# Current_sensor.net
KiCad netlist of a schematic drawn in EAGLE
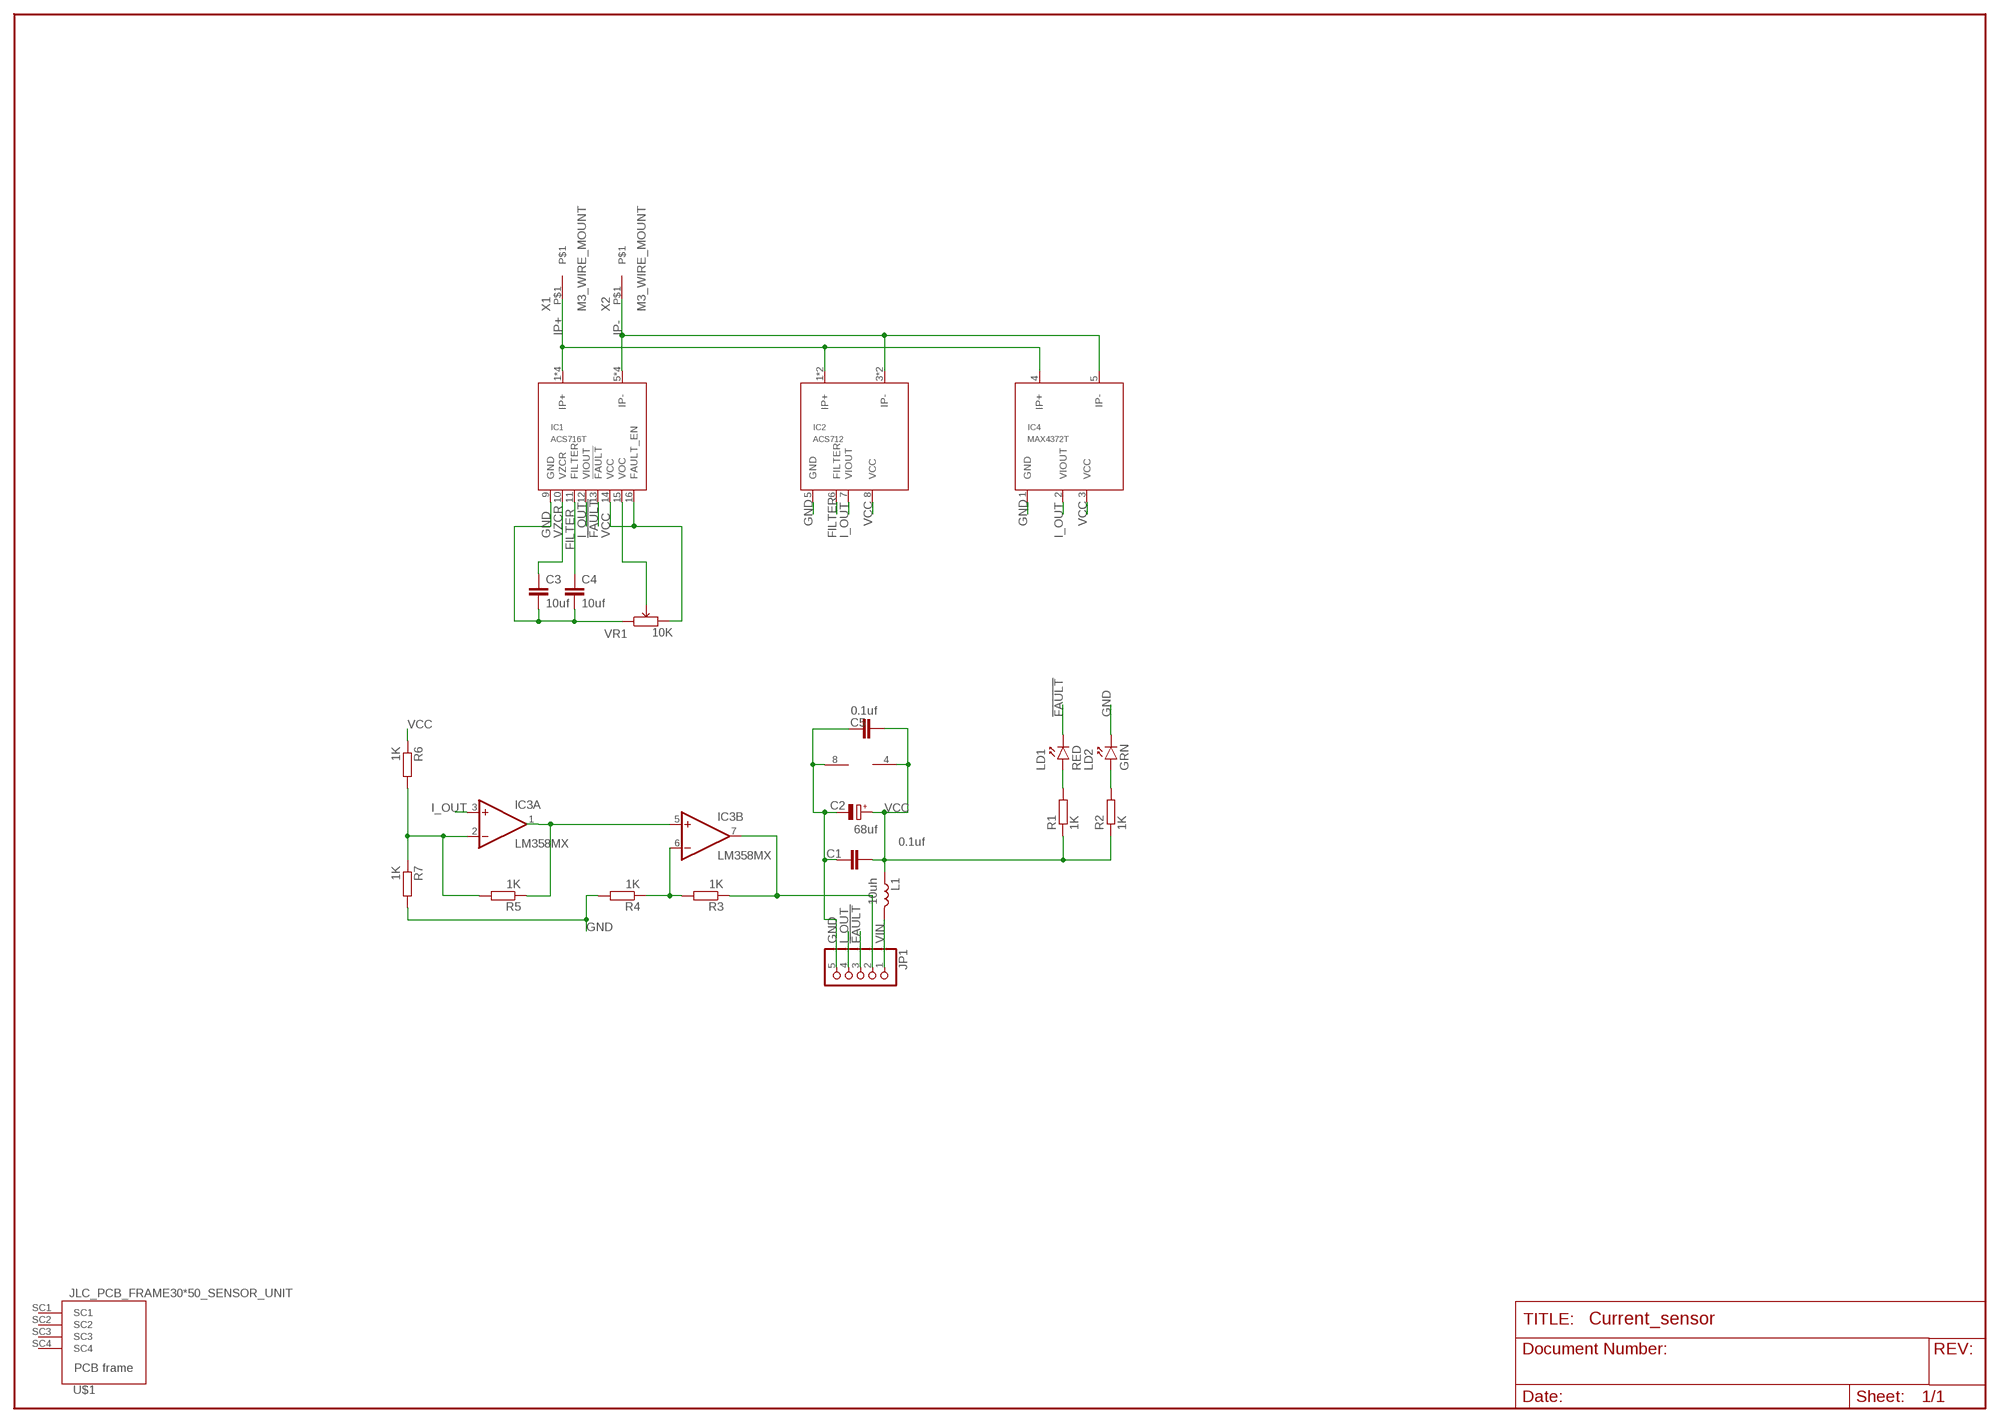
[diagram p0: schematic, sheet 1]

(export (version "E")
  (design (tool "Eeschema 10.0.6"))
  (components
    (comp (ref "C1")
      (value "0.1uf")
      (footprint "eagle-import:0603")
      (libsource (lib "eagle-import") (part "SMD_C0603"))
    )
    (comp (ref "C2")
      (value "68uf")
      (footprint "eagle-import:D_7343-31R")
      (libsource (lib "eagle-import") (part "TANTAL_686_7343"))
    )
    (comp (ref "C3")
      (value "10uf")
      (footprint "eagle-import:0805")
      (libsource (lib "eagle-import") (part "SMD_C0805"))
    )
    (comp (ref "C4")
      (value "10uf")
      (footprint "eagle-import:0805")
      (libsource (lib "eagle-import") (part "SMD_C0805"))
    )
    (comp (ref "C5")
      (value "0.1uf")
      (footprint "eagle-import:0603")
      (libsource (lib "eagle-import") (part "SMD_C0603"))
    )
    (comp (ref "IC1")
      (value "ACS716T")
      (footprint "eagle-import:SO16L")
      (libsource (lib "eagle-import") (part "ACS716T"))
    )
    (comp (ref "IC2")
      (value "ACS712")
      (footprint "eagle-import:SO8")
      (libsource (lib "eagle-import") (part "ACS712"))
    )
    (comp (ref "IC3")
      (value "LM358MX")
      (footprint "eagle-import:SO08")
      (libsource (lib "eagle-import") (part "LM358MX"))
    )
    (comp (ref "IC4")
      (value "MAX4372T")
      (footprint "eagle-import:SOT-23(5)")
      (libsource (lib "eagle-import") (part "MAX4372T"))
    )
    (comp (ref "JP1")
      (value "PINHD-1X55X2MM")
      (footprint "eagle-import:1_05X2MM")
      (libsource (lib "eagle-import") (part "PINHD-1X55X2MM"))
    )
    (comp (ref "L1")
      (value "10uh")
      (footprint "eagle-import:0603")
      (libsource (lib "eagle-import") (part "SMD_L0603"))
    )
    (comp (ref "LD1")
      (value "RED")
      (footprint "eagle-import:0603_P")
      (libsource (lib "eagle-import") (part "LED0603"))
    )
    (comp (ref "LD2")
      (value "GRN")
      (footprint "eagle-import:0603_P")
      (libsource (lib "eagle-import") (part "LED0603"))
    )
    (comp (ref "R1")
      (value "1K")
      (footprint "eagle-import:0603")
      (libsource (lib "eagle-import") (part "SMD_R0603"))
    )
    (comp (ref "R2")
      (value "1K")
      (footprint "eagle-import:0603")
      (libsource (lib "eagle-import") (part "SMD_R0603"))
    )
    (comp (ref "R3")
      (value "1K")
      (footprint "eagle-import:0603")
      (libsource (lib "eagle-import") (part "SMD_R0603"))
    )
    (comp (ref "R4")
      (value "1K")
      (footprint "eagle-import:0603")
      (libsource (lib "eagle-import") (part "SMD_R0603"))
    )
    (comp (ref "R5")
      (value "1K")
      (footprint "eagle-import:0603")
      (libsource (lib "eagle-import") (part "SMD_R0603"))
    )
    (comp (ref "R6")
      (value "1K")
      (footprint "eagle-import:0603")
      (libsource (lib "eagle-import") (part "SMD_R0603"))
    )
    (comp (ref "R7")
      (value "1K")
      (footprint "eagle-import:0603")
      (libsource (lib "eagle-import") (part "SMD_R0603"))
    )
    (comp (ref "U$1")
      (value "JLC_PCB_FRAME30*50_SENSOR_UNIT")
      (footprint "eagle-import:30X50_SENSOR_UNIT")
      (libsource (lib "eagle-import") (part "JLC_PCB_FRAME3050_SENSOR_UNIT"))
    )
    (comp (ref "VR1")
      (value "10K")
      (footprint "eagle-import:RESISTOR_VARIABLE")
      (libsource (lib "eagle-import") (part "POTENTIOMETER_SMD"))
    )
    (comp (ref "X1")
      (value "M3_WIRE_MOUNT")
      (footprint "eagle-import:M3_WIRE_MOUNT")
      (libsource (lib "eagle-import") (part "M3_WIRE_MOUNT"))
    )
    (comp (ref "X2")
      (value "M3_WIRE_MOUNT")
      (footprint "eagle-import:M3_WIRE_MOUNT")
      (libsource (lib "eagle-import") (part "M3_WIRE_MOUNT"))
    )
  )
  (nets
    (net (code "1") (name "/FILTER") (class "Default")
      (node (ref "C4") (pin "1") (pinfunction "1_1") (pintype "passive"))
      (node (ref "IC1") (pin "11") (pinfunction "FILTER_11") (pintype "bidirectional"))
      (node (ref "IC2") (pin "6") (pinfunction "FILTER_6") (pintype "bidirectional"))
    )
    (net (code "2") (name "/GND") (class "Default")
      (node (ref "C1") (pin "1") (pinfunction "1_1") (pintype "passive"))
      (node (ref "C2") (pin "-") (pinfunction "-_-") (pintype "passive"))
      (node (ref "C3") (pin "2") (pinfunction "2_2") (pintype "passive"))
      (node (ref "C4") (pin "2") (pinfunction "2_2") (pintype "passive"))
      (node (ref "C5") (pin "1") (pinfunction "1_1") (pintype "passive"))
      (node (ref "IC1") (pin "9") (pinfunction "GND_9") (pintype "bidirectional"))
      (node (ref "IC2") (pin "5") (pinfunction "GND_5") (pintype "bidirectional"))
      (node (ref "IC3") (pin "8") (pinfunction "V+_8") (pintype "power_in"))
      (node (ref "IC4") (pin "1") (pinfunction "GND_1") (pintype "bidirectional"))
      (node (ref "JP1") (pin "5") (pinfunction "5_5") (pintype "passive"))
      (node (ref "LD2") (pin "1") (pinfunction "K_1") (pintype "bidirectional"))
      (node (ref "R4") (pin "2") (pinfunction "2_2") (pintype "passive"))
      (node (ref "R7") (pin "2") (pinfunction "2_2") (pintype "passive"))
      (node (ref "VR1") (pin "L") (pinfunction "L_L") (pintype "passive"))
    )
    (net (code "3") (name "/IP+") (class "Default")
      (node (ref "IC1") (pin "1") (pinfunction "IP+_1") (pintype "bidirectional"))
      (node (ref "IC1") (pin "2") (pinfunction "IP+_2") (pintype "bidirectional"))
      (node (ref "IC1") (pin "3") (pinfunction "IP+_3") (pintype "bidirectional"))
      (node (ref "IC1") (pin "4") (pinfunction "IP+_4") (pintype "bidirectional"))
      (node (ref "IC2") (pin "1") (pinfunction "IP+_1") (pintype "bidirectional"))
      (node (ref "IC2") (pin "2") (pinfunction "IP+_2") (pintype "bidirectional"))
      (node (ref "IC4") (pin "4") (pinfunction "IP+_4") (pintype "bidirectional"))
      (node (ref "X1") (pin "P$1") (pinfunction "P$1_P$1") (pintype "bidirectional"))
    )
    (net (code "4") (name "/IP-") (class "Default")
      (node (ref "IC1") (pin "5") (pinfunction "IP-_5") (pintype "bidirectional"))
      (node (ref "IC1") (pin "6") (pinfunction "IP-_6") (pintype "bidirectional"))
      (node (ref "IC1") (pin "7") (pinfunction "IP-_7") (pintype "bidirectional"))
      (node (ref "IC1") (pin "8") (pinfunction "IP-_8") (pintype "bidirectional"))
      (node (ref "IC2") (pin "3") (pinfunction "IP-_3") (pintype "bidirectional"))
      (node (ref "IC2") (pin "4") (pinfunction "IP-_4") (pintype "bidirectional"))
      (node (ref "IC4") (pin "5") (pinfunction "IP-_5") (pintype "bidirectional"))
      (node (ref "X2") (pin "P$1") (pinfunction "P$1_P$1") (pintype "bidirectional"))
    )
    (net (code "5") (name "/I_OUT") (class "Default")
      (node (ref "IC1") (pin "12") (pinfunction "VIOUT_12") (pintype "bidirectional"))
      (node (ref "IC2") (pin "7") (pinfunction "VIOUT_7") (pintype "bidirectional"))
      (node (ref "IC3") (pin "3") (pinfunction "+IN_3") (pintype "input"))
      (node (ref "IC4") (pin "2") (pinfunction "VIOUT_2") (pintype "bidirectional"))
      (node (ref "JP1") (pin "4") (pinfunction "4_4") (pintype "passive"))
    )
    (net (code "6") (name "/VCC") (class "Default")
      (node (ref "C1") (pin "2") (pinfunction "2_2") (pintype "passive"))
      (node (ref "C2") (pin "+") (pinfunction "+_+") (pintype "passive"))
      (node (ref "C5") (pin "2") (pinfunction "2_2") (pintype "passive"))
      (node (ref "IC1") (pin "14") (pinfunction "VCC_14") (pintype "bidirectional"))
      (node (ref "IC1") (pin "16") (pinfunction "FAULT_EN_16") (pintype "bidirectional"))
      (node (ref "IC2") (pin "8") (pinfunction "VCC_8") (pintype "bidirectional"))
      (node (ref "IC3") (pin "4") (pinfunction "V-_4") (pintype "power_in"))
      (node (ref "IC4") (pin "3") (pinfunction "VCC_3") (pintype "bidirectional"))
      (node (ref "L1") (pin "1") (pinfunction "1_1") (pintype "passive"))
      (node (ref "R1") (pin "1") (pinfunction "1_1") (pintype "passive"))
      (node (ref "R2") (pin "1") (pinfunction "1_1") (pintype "passive"))
      (node (ref "R6") (pin "1") (pinfunction "1_1") (pintype "passive"))
      (node (ref "VR1") (pin "H") (pinfunction "H_H") (pintype "passive"))
    )
    (net (code "7") (name "/VIN") (class "Default")
      (node (ref "JP1") (pin "1") (pinfunction "1_1") (pintype "passive"))
      (node (ref "L1") (pin "2") (pinfunction "2_2") (pintype "passive"))
    )
    (net (code "8") (name "/VZCR") (class "Default")
      (node (ref "C3") (pin "1") (pinfunction "1_1") (pintype "passive"))
      (node (ref "IC1") (pin "10") (pinfunction "VZCR_10") (pintype "bidirectional"))
    )
    (net (code "9") (name "/~{FAULT}") (class "Default")
      (node (ref "IC1") (pin "13") (pinfunction "~{FAULT}_13") (pintype "bidirectional"))
      (node (ref "JP1") (pin "3") (pinfunction "3_3") (pintype "passive"))
      (node (ref "LD1") (pin "1") (pinfunction "K_1") (pintype "bidirectional"))
    )
    (net (code "10") (name "Net-(IC1-VOC)") (class "Default")
      (node (ref "IC1") (pin "15") (pinfunction "VOC_15") (pintype "bidirectional"))
      (node (ref "VR1") (pin "W") (pinfunction "W_W") (pintype "bidirectional"))
    )
    (net (code "11") (name "Net-(IC3A--IN)") (class "Default")
      (node (ref "IC3") (pin "2") (pinfunction "-IN_2") (pintype "input"))
      (node (ref "R5") (pin "2") (pinfunction "2_2") (pintype "passive"))
      (node (ref "R6") (pin "2") (pinfunction "2_2") (pintype "passive"))
      (node (ref "R7") (pin "1") (pinfunction "1_1") (pintype "passive"))
    )
    (net (code "12") (name "Net-(IC3A-OUT)") (class "Default")
      (node (ref "IC3") (pin "1") (pinfunction "OUT_1") (pintype "output"))
      (node (ref "IC3") (pin "5") (pinfunction "+IN_5") (pintype "input"))
      (node (ref "R5") (pin "1") (pinfunction "1_1") (pintype "passive"))
    )
    (net (code "13") (name "Net-(IC3B--IN)") (class "Default")
      (node (ref "IC3") (pin "6") (pinfunction "-IN_6") (pintype "input"))
      (node (ref "R3") (pin "2") (pinfunction "2_2") (pintype "passive"))
      (node (ref "R4") (pin "1") (pinfunction "1_1") (pintype "passive"))
    )
    (net (code "14") (name "Net-(IC3B-OUT)") (class "Default")
      (node (ref "IC3") (pin "7") (pinfunction "OUT_7") (pintype "output"))
      (node (ref "JP1") (pin "2") (pinfunction "2_2") (pintype "passive"))
      (node (ref "R3") (pin "1") (pinfunction "1_1") (pintype "passive"))
    )
    (net (code "15") (name "Net-(LD1-A)") (class "Default")
      (node (ref "LD1") (pin "2") (pinfunction "A_2") (pintype "bidirectional"))
      (node (ref "R1") (pin "2") (pinfunction "2_2") (pintype "passive"))
    )
    (net (code "16") (name "Net-(LD2-A)") (class "Default")
      (node (ref "LD2") (pin "2") (pinfunction "A_2") (pintype "bidirectional"))
      (node (ref "R2") (pin "2") (pinfunction "2_2") (pintype "passive"))
    )
    (net (code "17") (name "unconnected-(U$1-PadSC1)") (class "Default")
      (node (ref "U$1") (pin "SC1") (pinfunction "SC1_SC1") (pintype "bidirectional"))
    )
    (net (code "18") (name "unconnected-(U$1-PadSC2)") (class "Default")
      (node (ref "U$1") (pin "SC2") (pinfunction "SC2_SC2") (pintype "bidirectional"))
    )
    (net (code "19") (name "unconnected-(U$1-PadSC3)") (class "Default")
      (node (ref "U$1") (pin "SC3") (pinfunction "SC3_SC3") (pintype "bidirectional"))
    )
    (net (code "20") (name "unconnected-(U$1-PadSC4)") (class "Default")
      (node (ref "U$1") (pin "SC4") (pinfunction "SC4_SC4") (pintype "bidirectional"))
    )
  )
)
